# InputModule.net
KiCad netlist of a schematic drawn in Altium Designer
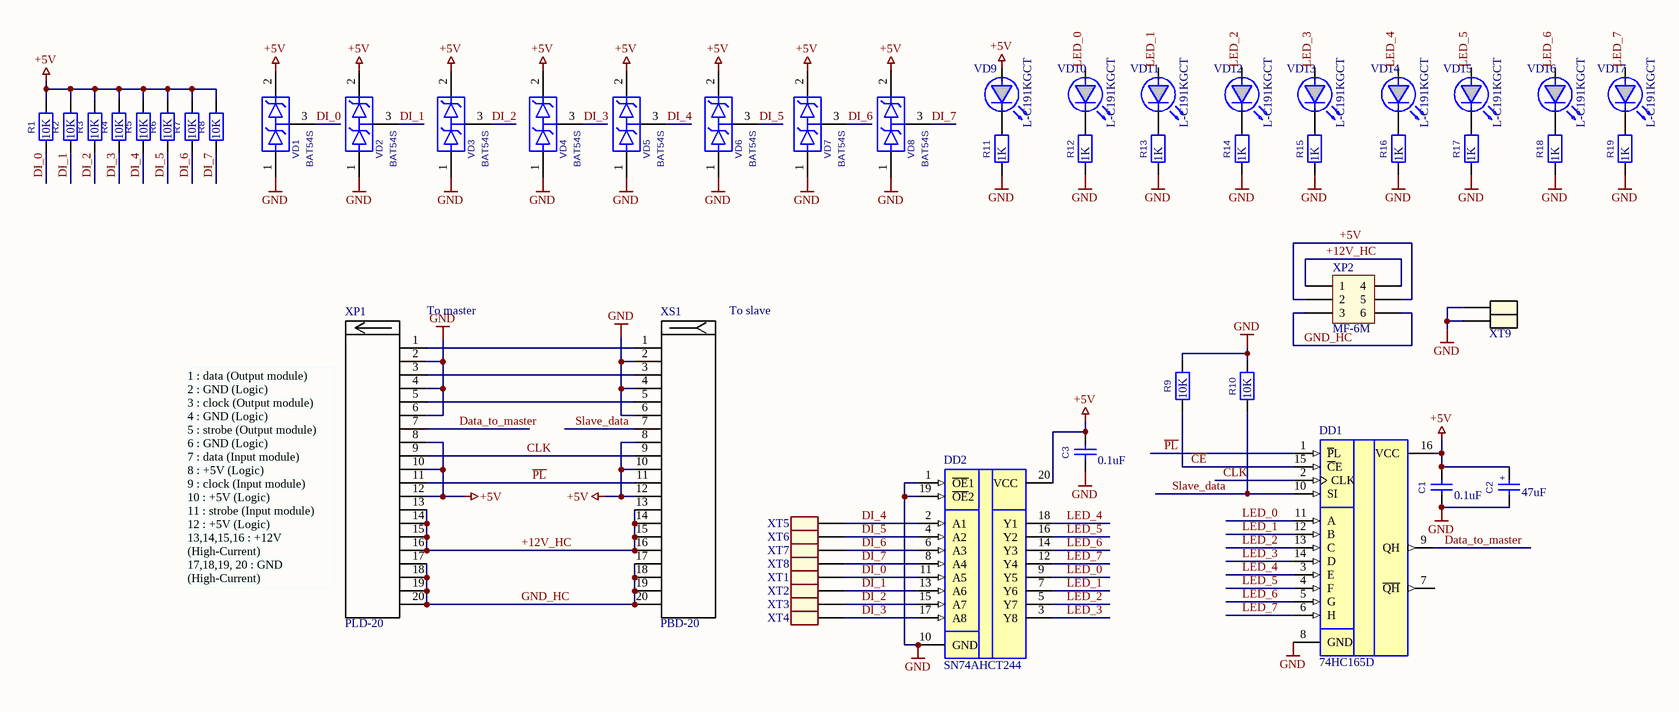
[diagram p0: InputModule.SchDoc]

(export (version "E")
  (design (tool "Eeschema 10.0.6"))
  (components
    (comp (ref "C1")
      (value "0.1uF")
      (footprint "C-1608[0603]")
      (description "C-0603")
      (libsource (lib "Altium-RC") (part "C-0603"))
    )
    (comp (ref "C2")
      (value "47uF")
      (footprint "C-CASE")
      (description "C-CCASE")
      (libsource (lib "Altium-RC") (part "C-CCASE"))
    )
    (comp (ref "C3")
      (value "0.1uF")
      (footprint "C-1608[0603]")
      (description "C-0603")
      (libsource (lib "Altium-RC") (part "C-0603"))
    )
    (comp (ref "DD1")
      (value "74HC165D")
      (footprint "SO-G16")
      (description "8-Bit Parallel-Load Shift Register")
      (libsource (lib "Altium-IC") (part "74HC165D"))
    )
    (comp (ref "DD2")
      (value "SN74AHCT244")
      (footprint "TSSOP20")
      (description "Octal Buffer/Driver with 3-State Outputs")
      (libsource (lib "Altium-IC") (part "SN74LVC244APW"))
    )
    (comp (ref "R1")
      (value "10K")
      (footprint "R-1608[0603]")
      (description "R-0603")
      (libsource (lib "Altium-RC") (part "R-0603"))
    )
    (comp (ref "R2")
      (value "10K")
      (footprint "R-1608[0603]")
      (description "R-0603")
      (libsource (lib "Altium-RC") (part "R-0603"))
    )
    (comp (ref "R3")
      (value "10K")
      (footprint "R-1608[0603]")
      (description "R-0603")
      (libsource (lib "Altium-RC") (part "R-0603"))
    )
    (comp (ref "R4")
      (value "10K")
      (footprint "R-1608[0603]")
      (description "R-0603")
      (libsource (lib "Altium-RC") (part "R-0603"))
    )
    (comp (ref "R5")
      (value "10K")
      (footprint "R-1608[0603]")
      (description "R-0603")
      (libsource (lib "Altium-RC") (part "R-0603"))
    )
    (comp (ref "R6")
      (value "10K")
      (footprint "R-1608[0603]")
      (description "R-0603")
      (libsource (lib "Altium-RC") (part "R-0603"))
    )
    (comp (ref "R7")
      (value "10K")
      (footprint "R-1608[0603]")
      (description "R-0603")
      (libsource (lib "Altium-RC") (part "R-0603"))
    )
    (comp (ref "R8")
      (value "10K")
      (footprint "R-1608[0603]")
      (description "R-0603")
      (libsource (lib "Altium-RC") (part "R-0603"))
    )
    (comp (ref "R9")
      (value "10K")
      (footprint "R-1608[0603]")
      (description "R-0603")
      (libsource (lib "Altium-RC") (part "R-0603"))
    )
    (comp (ref "R10")
      (value "10K")
      (footprint "R-1608[0603]")
      (description "R-0603")
      (libsource (lib "Altium-RC") (part "R-0603"))
    )
    (comp (ref "R11")
      (value "1K")
      (footprint "R-1608[0603]")
      (description "R-0603")
      (libsource (lib "Altium-RC") (part "R-0603"))
    )
    (comp (ref "R12")
      (value "1K")
      (footprint "R-1608[0603]")
      (description "R-0603")
      (libsource (lib "Altium-RC") (part "R-0603"))
    )
    (comp (ref "R13")
      (value "1K")
      (footprint "R-1608[0603]")
      (description "R-0603")
      (libsource (lib "Altium-RC") (part "R-0603"))
    )
    (comp (ref "R14")
      (value "1K")
      (footprint "R-1608[0603]")
      (description "R-0603")
      (libsource (lib "Altium-RC") (part "R-0603"))
    )
    (comp (ref "R15")
      (value "1K")
      (footprint "R-1608[0603]")
      (description "R-0603")
      (libsource (lib "Altium-RC") (part "R-0603"))
    )
    (comp (ref "R16")
      (value "1K")
      (footprint "R-1608[0603]")
      (description "R-0603")
      (libsource (lib "Altium-RC") (part "R-0603"))
    )
    (comp (ref "R17")
      (value "1K")
      (footprint "R-1608[0603]")
      (description "R-0603")
      (libsource (lib "Altium-RC") (part "R-0603"))
    )
    (comp (ref "R18")
      (value "1K")
      (footprint "R-1608[0603]")
      (description "R-0603")
      (libsource (lib "Altium-RC") (part "R-0603"))
    )
    (comp (ref "R19")
      (value "1K")
      (footprint "R-1608[0603]")
      (description "R-0603")
      (libsource (lib "Altium-RC") (part "R-0603"))
    )
    (comp (ref "VD1")
      (value "BAT54S")
      (footprint "SOT-23")
      (description "Schottky barrier (double) diodes")
      (libsource (lib "Altium-RECT") (part "BAT54S"))
    )
    (comp (ref "VD2")
      (value "BAT54S")
      (footprint "SOT-23")
      (description "Schottky barrier (double) diodes")
      (libsource (lib "Altium-RECT") (part "BAT54S"))
    )
    (comp (ref "VD3")
      (value "BAT54S")
      (footprint "SOT-23")
      (description "Schottky barrier (double) diodes")
      (libsource (lib "Altium-RECT") (part "BAT54S"))
    )
    (comp (ref "VD4")
      (value "BAT54S")
      (footprint "SOT-23")
      (description "Schottky barrier (double) diodes")
      (libsource (lib "Altium-RECT") (part "BAT54S"))
    )
    (comp (ref "VD5")
      (value "BAT54S")
      (footprint "SOT-23")
      (description "Schottky barrier (double) diodes")
      (libsource (lib "Altium-RECT") (part "BAT54S"))
    )
    (comp (ref "VD6")
      (value "BAT54S")
      (footprint "SOT-23")
      (description "Schottky barrier (double) diodes")
      (libsource (lib "Altium-RECT") (part "BAT54S"))
    )
    (comp (ref "VD7")
      (value "BAT54S")
      (footprint "SOT-23")
      (description "Schottky barrier (double) diodes")
      (libsource (lib "Altium-RECT") (part "BAT54S"))
    )
    (comp (ref "VD8")
      (value "BAT54S")
      (footprint "SOT-23")
      (description "Schottky barrier (double) diodes")
      (libsource (lib "Altium-RECT") (part "BAT54S"))
    )
    (comp (ref "VD9")
      (value "L-C191KGCT")
      (footprint "LED-0603")
      (description "0603 Green Led")
      (libsource (lib "Altium-OPTO") (part "L-C191KGCT"))
    )
    (comp (ref "VD10")
      (value "L-C191KGCT")
      (footprint "LED-0603")
      (description "0603 Green Led")
      (libsource (lib "Altium-OPTO") (part "L-C191KGCT"))
    )
    (comp (ref "VD11")
      (value "L-C191KGCT")
      (footprint "LED-0603")
      (description "0603 Green Led")
      (libsource (lib "Altium-OPTO") (part "L-C191KGCT"))
    )
    (comp (ref "VD12")
      (value "L-C191KGCT")
      (footprint "LED-0603")
      (description "0603 Green Led")
      (libsource (lib "Altium-OPTO") (part "L-C191KGCT"))
    )
    (comp (ref "VD13")
      (value "L-C191KGCT")
      (footprint "LED-0603")
      (description "0603 Green Led")
      (libsource (lib "Altium-OPTO") (part "L-C191KGCT"))
    )
    (comp (ref "VD14")
      (value "L-C191KGCT")
      (footprint "LED-0603")
      (description "0603 Green Led")
      (libsource (lib "Altium-OPTO") (part "L-C191KGCT"))
    )
    (comp (ref "VD15")
      (value "L-C191KGCT")
      (footprint "LED-0603")
      (description "0603 Green Led")
      (libsource (lib "Altium-OPTO") (part "L-C191KGCT"))
    )
    (comp (ref "VD16")
      (value "L-C191KGCT")
      (footprint "LED-0603")
      (description "0603 Green Led")
      (libsource (lib "Altium-OPTO") (part "L-C191KGCT"))
    )
    (comp (ref "VD17")
      (value "L-C191KGCT")
      (footprint "LED-0603")
      (description "0603 Green Led")
      (libsource (lib "Altium-OPTO") (part "L-C191KGCT"))
    )
    (comp (ref "XP1")
      (value "PLD-20")
      (footprint "PLD-20 ROT")
      (description "20 pin, 2 row, MALE connector")
      (libsource (lib "Altium-CONN") (part "PLD-20"))
    )
    (comp (ref "XP2")
      (value "MF-6M")
      (footprint "MF-6M")
      (description "Molex Male connector")
      (libsource (lib "Altium-CONN") (part "MF-6M"))
    )
    (comp (ref "XS1")
      (value "PBD-20")
      (footprint "PBD-20 Rot")
      (description "2.54mm, 20 pin FEMALE connector")
      (libsource (lib "Altium-CONN") (part "PBD-20"))
    )
    (comp (ref "XT1")
      (value "DG141V-01P")
      (footprint "DG141V-01P (XY123R)")
      (description "Клеммник нажимной 2.54мм")
      (libsource (lib "Altium-CONN") (part "DG141V-01P"))
    )
    (comp (ref "XT2")
      (value "DG141V-01P")
      (footprint "DG141V-01P (XY123R)")
      (description "Клеммник нажимной 2.54мм")
      (libsource (lib "Altium-CONN") (part "DG141V-01P"))
    )
    (comp (ref "XT3")
      (value "DG141V-01P")
      (footprint "DG141V-01P (XY123R)")
      (description "Клеммник нажимной 2.54мм")
      (libsource (lib "Altium-CONN") (part "DG141V-01P"))
    )
    (comp (ref "XT4")
      (value "DG141V-01P")
      (footprint "DG141V-01P (XY123R)")
      (description "Клеммник нажимной 2.54мм")
      (libsource (lib "Altium-CONN") (part "DG141V-01P"))
    )
    (comp (ref "XT5")
      (value "DG141V-01P")
      (footprint "DG141V-01P (XY123R)")
      (description "Клеммник нажимной 2.54мм")
      (libsource (lib "Altium-CONN") (part "DG141V-01P"))
    )
    (comp (ref "XT6")
      (value "DG141V-01P")
      (footprint "DG141V-01P (XY123R)")
      (description "Клеммник нажимной 2.54мм")
      (libsource (lib "Altium-CONN") (part "DG141V-01P"))
    )
    (comp (ref "XT7")
      (value "DG141V-01P")
      (footprint "DG141V-01P (XY123R)")
      (description "Клеммник нажимной 2.54мм")
      (libsource (lib "Altium-CONN") (part "DG141V-01P"))
    )
    (comp (ref "XT8")
      (value "DG141V-01P")
      (footprint "DG141V-01P (XY123R)")
      (description "Клеммник нажимной 2.54мм")
      (libsource (lib "Altium-CONN") (part "DG141V-01P"))
    )
    (comp (ref "XT9")
      (value "1-1776244-0 (TYCO)")
      (footprint "1-1776244-0")
      (description "Винтовой клеммник 5.0мм")
      (libsource (lib "Altium-CONN") (part "1-1776244-0 (TYCO)"))
    )
  )
  (nets
    (net (code "1") (name "+5V") (class "Default")
      (node (ref "C1") (pin "1") (pintype "passive"))
      (node (ref "C2") (pin "1") (pinfunction "+_1") (pintype "passive"))
      (node (ref "C3") (pin "1") (pintype "passive"))
      (node (ref "DD1") (pin "16") (pinfunction "VCC_16") (pintype "power_in"))
      (node (ref "DD2") (pin "20") (pinfunction "VCC_20") (pintype "power_in"))
      (node (ref "R1") (pin "2") (pinfunction "2_2") (pintype "passive"))
      (node (ref "R2") (pin "2") (pinfunction "2_2") (pintype "passive"))
      (node (ref "R3") (pin "2") (pinfunction "2_2") (pintype "passive"))
      (node (ref "R4") (pin "2") (pinfunction "2_2") (pintype "passive"))
      (node (ref "R5") (pin "2") (pinfunction "2_2") (pintype "passive"))
      (node (ref "R6") (pin "2") (pinfunction "2_2") (pintype "passive"))
      (node (ref "R7") (pin "2") (pinfunction "2_2") (pintype "passive"))
      (node (ref "R8") (pin "2") (pinfunction "2_2") (pintype "passive"))
      (node (ref "VD1") (pin "2") (pinfunction "c_2") (pintype "passive"))
      (node (ref "VD2") (pin "2") (pinfunction "c_2") (pintype "passive"))
      (node (ref "VD3") (pin "2") (pinfunction "c_2") (pintype "passive"))
      (node (ref "VD4") (pin "2") (pinfunction "c_2") (pintype "passive"))
      (node (ref "VD5") (pin "2") (pinfunction "c_2") (pintype "passive"))
      (node (ref "VD6") (pin "2") (pinfunction "c_2") (pintype "passive"))
      (node (ref "VD7") (pin "2") (pinfunction "c_2") (pintype "passive"))
      (node (ref "VD8") (pin "2") (pinfunction "c_2") (pintype "passive"))
      (node (ref "VD9") (pin "2") (pinfunction "A_2") (pintype "passive"))
      (node (ref "XP1") (pin "10") (pintype "passive"))
      (node (ref "XP1") (pin "12") (pintype "passive"))
      (node (ref "XP1") (pin "8") (pintype "passive"))
      (node (ref "XP2") (pin "2") (pinfunction "2_2") (pintype "passive"))
      (node (ref "XP2") (pin "5") (pinfunction "5_5") (pintype "passive"))
      (node (ref "XS1") (pin "10") (pintype "passive"))
      (node (ref "XS1") (pin "12") (pintype "passive"))
      (node (ref "XS1") (pin "8") (pintype "passive"))
    )
    (net (code "2") (name "/+12V_HC") (class "Default")
      (node (ref "XP1") (pin "13") (pintype "passive"))
      (node (ref "XP1") (pin "14") (pintype "passive"))
      (node (ref "XP1") (pin "15") (pintype "passive"))
      (node (ref "XP1") (pin "16") (pintype "passive"))
      (node (ref "XP2") (pin "1") (pinfunction "1_1") (pintype "passive"))
      (node (ref "XP2") (pin "4") (pinfunction "4_4") (pintype "passive"))
      (node (ref "XS1") (pin "13") (pintype "passive"))
      (node (ref "XS1") (pin "14") (pintype "passive"))
      (node (ref "XS1") (pin "15") (pintype "passive"))
      (node (ref "XS1") (pin "16") (pintype "passive"))
    )
    (net (code "3") (name "/CLK") (class "Default")
      (node (ref "DD1") (pin "2") (pinfunction "CLK_2") (pintype "input"))
      (node (ref "XP1") (pin "9") (pintype "passive"))
      (node (ref "XS1") (pin "9") (pintype "passive"))
    )
    (net (code "4") (name "/DI_0") (class "Default")
      (node (ref "DD2") (pin "11") (pinfunction "A5_11") (pintype "input"))
      (node (ref "R1") (pin "1") (pinfunction "1_1") (pintype "passive"))
      (node (ref "VD1") (pin "3") (pinfunction "ka_3") (pintype "passive"))
      (node (ref "XT1") (pin "1") (pintype "passive"))
    )
    (net (code "5") (name "/DI_1") (class "Default")
      (node (ref "DD2") (pin "13") (pinfunction "A6_13") (pintype "input"))
      (node (ref "R2") (pin "1") (pinfunction "1_1") (pintype "passive"))
      (node (ref "VD2") (pin "3") (pinfunction "ka_3") (pintype "passive"))
      (node (ref "XT2") (pin "1") (pintype "passive"))
    )
    (net (code "6") (name "/DI_2") (class "Default")
      (node (ref "DD2") (pin "15") (pinfunction "A7_15") (pintype "input"))
      (node (ref "R3") (pin "1") (pinfunction "1_1") (pintype "passive"))
      (node (ref "VD3") (pin "3") (pinfunction "ka_3") (pintype "passive"))
      (node (ref "XT3") (pin "1") (pintype "passive"))
    )
    (net (code "7") (name "/DI_3") (class "Default")
      (node (ref "DD2") (pin "17") (pinfunction "A8_17") (pintype "input"))
      (node (ref "R4") (pin "1") (pinfunction "1_1") (pintype "passive"))
      (node (ref "VD4") (pin "3") (pinfunction "ka_3") (pintype "passive"))
      (node (ref "XT4") (pin "1") (pintype "passive"))
    )
    (net (code "8") (name "/DI_4") (class "Default")
      (node (ref "DD2") (pin "2") (pinfunction "A1_2") (pintype "input"))
      (node (ref "R5") (pin "1") (pinfunction "1_1") (pintype "passive"))
      (node (ref "VD5") (pin "3") (pinfunction "ka_3") (pintype "passive"))
      (node (ref "XT5") (pin "1") (pintype "passive"))
    )
    (net (code "9") (name "/DI_5") (class "Default")
      (node (ref "DD2") (pin "4") (pinfunction "A2_4") (pintype "input"))
      (node (ref "R6") (pin "1") (pinfunction "1_1") (pintype "passive"))
      (node (ref "VD6") (pin "3") (pinfunction "ka_3") (pintype "passive"))
      (node (ref "XT6") (pin "1") (pintype "passive"))
    )
    (net (code "10") (name "/DI_6") (class "Default")
      (node (ref "DD2") (pin "6") (pinfunction "A3_6") (pintype "input"))
      (node (ref "R7") (pin "1") (pinfunction "1_1") (pintype "passive"))
      (node (ref "VD7") (pin "3") (pinfunction "ka_3") (pintype "passive"))
      (node (ref "XT7") (pin "1") (pintype "passive"))
    )
    (net (code "11") (name "/DI_7") (class "Default")
      (node (ref "DD2") (pin "8") (pinfunction "A4_8") (pintype "input"))
      (node (ref "R8") (pin "1") (pinfunction "1_1") (pintype "passive"))
      (node (ref "VD8") (pin "3") (pinfunction "ka_3") (pintype "passive"))
      (node (ref "XT8") (pin "1") (pintype "passive"))
    )
    (net (code "12") (name "/Data_to_master") (class "Default")
      (node (ref "DD1") (pin "9") (pinfunction "QH_9") (pintype "output"))
      (node (ref "XP1") (pin "7") (pintype "passive"))
    )
    (net (code "13") (name "/GND_HC") (class "Default")
      (node (ref "XP1") (pin "17") (pintype "passive"))
      (node (ref "XP1") (pin "18") (pintype "passive"))
      (node (ref "XP1") (pin "19") (pintype "passive"))
      (node (ref "XP1") (pin "20") (pintype "passive"))
      (node (ref "XP2") (pin "3") (pinfunction "3_3") (pintype "passive"))
      (node (ref "XP2") (pin "6") (pinfunction "6_6") (pintype "passive"))
      (node (ref "XS1") (pin "17") (pintype "passive"))
      (node (ref "XS1") (pin "18") (pintype "passive"))
      (node (ref "XS1") (pin "19") (pintype "passive"))
      (node (ref "XS1") (pin "20") (pintype "passive"))
    )
    (net (code "14") (name "/LED_0") (class "Default")
      (node (ref "DD1") (pin "11") (pinfunction "A_11") (pintype "input"))
      (node (ref "DD2") (pin "9") (pinfunction "Y5_9") (pintype "tri_state"))
      (node (ref "VD10") (pin "2") (pinfunction "A_2") (pintype "passive"))
    )
    (net (code "15") (name "/LED_1") (class "Default")
      (node (ref "DD1") (pin "12") (pinfunction "B_12") (pintype "input"))
      (node (ref "DD2") (pin "7") (pinfunction "Y6_7") (pintype "tri_state"))
      (node (ref "VD11") (pin "2") (pinfunction "A_2") (pintype "passive"))
    )
    (net (code "16") (name "/LED_2") (class "Default")
      (node (ref "DD1") (pin "13") (pinfunction "C_13") (pintype "input"))
      (node (ref "DD2") (pin "5") (pinfunction "Y7_5") (pintype "tri_state"))
      (node (ref "VD12") (pin "2") (pinfunction "A_2") (pintype "passive"))
    )
    (net (code "17") (name "/LED_3") (class "Default")
      (node (ref "DD1") (pin "14") (pinfunction "D_14") (pintype "input"))
      (node (ref "DD2") (pin "3") (pinfunction "Y8_3") (pintype "tri_state"))
      (node (ref "VD13") (pin "2") (pinfunction "A_2") (pintype "passive"))
    )
    (net (code "18") (name "/LED_4") (class "Default")
      (node (ref "DD1") (pin "3") (pinfunction "E_3") (pintype "input"))
      (node (ref "DD2") (pin "18") (pinfunction "Y1_18") (pintype "tri_state"))
      (node (ref "VD14") (pin "2") (pinfunction "A_2") (pintype "passive"))
    )
    (net (code "19") (name "/LED_5") (class "Default")
      (node (ref "DD1") (pin "4") (pinfunction "F_4") (pintype "input"))
      (node (ref "DD2") (pin "16") (pinfunction "Y2_16") (pintype "tri_state"))
      (node (ref "VD15") (pin "2") (pinfunction "A_2") (pintype "passive"))
    )
    (net (code "20") (name "/LED_6") (class "Default")
      (node (ref "DD1") (pin "5") (pinfunction "G_5") (pintype "input"))
      (node (ref "DD2") (pin "14") (pinfunction "Y3_14") (pintype "tri_state"))
      (node (ref "VD16") (pin "2") (pinfunction "A_2") (pintype "passive"))
    )
    (net (code "21") (name "/LED_7") (class "Default")
      (node (ref "DD1") (pin "6") (pinfunction "H_6") (pintype "input"))
      (node (ref "DD2") (pin "12") (pinfunction "Y4_12") (pintype "tri_state"))
      (node (ref "VD17") (pin "2") (pinfunction "A_2") (pintype "passive"))
    )
    (net (code "22") (name "/Slave_data") (class "Default")
      (node (ref "DD1") (pin "10") (pinfunction "SI_10") (pintype "input"))
      (node (ref "R10") (pin "1") (pinfunction "1_1") (pintype "passive"))
      (node (ref "XS1") (pin "7") (pintype "passive"))
    )
    (net (code "23") (name "/~{CE}") (class "Default")
      (node (ref "DD1") (pin "15") (pinfunction "~{C}E_15") (pintype "input"))
      (node (ref "R9") (pin "1") (pinfunction "1_1") (pintype "passive"))
    )
    (net (code "24") (name "/~{PL}") (class "Default")
      (node (ref "DD1") (pin "1") (pinfunction "~{P}L_1") (pintype "input"))
      (node (ref "XP1") (pin "11") (pintype "passive"))
      (node (ref "XS1") (pin "11") (pintype "passive"))
    )
    (net (code "25") (name "GND") (class "Default")
      (node (ref "C1") (pin "2") (pintype "passive"))
      (node (ref "C2") (pin "2") (pinfunction "-_2") (pintype "passive"))
      (node (ref "C3") (pin "2") (pintype "passive"))
      (node (ref "DD1") (pin "8") (pinfunction "GND_8") (pintype "power_in"))
      (node (ref "DD2") (pin "1") (pinfunction "~{OE}1_1") (pintype "input"))
      (node (ref "DD2") (pin "10") (pinfunction "GND_10") (pintype "power_in"))
      (node (ref "DD2") (pin "19") (pinfunction "~{OE}2_19") (pintype "input"))
      (node (ref "R10") (pin "2") (pinfunction "2_2") (pintype "passive"))
      (node (ref "R11") (pin "1") (pinfunction "1_1") (pintype "passive"))
      (node (ref "R12") (pin "1") (pinfunction "1_1") (pintype "passive"))
      (node (ref "R13") (pin "1") (pinfunction "1_1") (pintype "passive"))
      (node (ref "R14") (pin "1") (pinfunction "1_1") (pintype "passive"))
      (node (ref "R15") (pin "1") (pinfunction "1_1") (pintype "passive"))
      (node (ref "R16") (pin "1") (pinfunction "1_1") (pintype "passive"))
      (node (ref "R17") (pin "1") (pinfunction "1_1") (pintype "passive"))
      (node (ref "R18") (pin "1") (pinfunction "1_1") (pintype "passive"))
      (node (ref "R19") (pin "1") (pinfunction "1_1") (pintype "passive"))
      (node (ref "R9") (pin "2") (pinfunction "2_2") (pintype "passive"))
      (node (ref "VD1") (pin "1") (pinfunction "a_1") (pintype "passive"))
      (node (ref "VD2") (pin "1") (pinfunction "a_1") (pintype "passive"))
      (node (ref "VD3") (pin "1") (pinfunction "a_1") (pintype "passive"))
      (node (ref "VD4") (pin "1") (pinfunction "a_1") (pintype "passive"))
      (node (ref "VD5") (pin "1") (pinfunction "a_1") (pintype "passive"))
      (node (ref "VD6") (pin "1") (pinfunction "a_1") (pintype "passive"))
      (node (ref "VD7") (pin "1") (pinfunction "a_1") (pintype "passive"))
      (node (ref "VD8") (pin "1") (pinfunction "a_1") (pintype "passive"))
      (node (ref "XP1") (pin "2") (pintype "passive"))
      (node (ref "XP1") (pin "4") (pintype "passive"))
      (node (ref "XP1") (pin "6") (pintype "passive"))
      (node (ref "XS1") (pin "2") (pintype "passive"))
      (node (ref "XS1") (pin "4") (pintype "passive"))
      (node (ref "XS1") (pin "6") (pintype "passive"))
      (node (ref "XT9") (pin "1") (pintype "passive"))
      (node (ref "XT9") (pin "2") (pintype "passive"))
    )
    (net (code "26") (name "Net-(VD9-K)") (class "Default")
      (node (ref "R11") (pin "2") (pinfunction "2_2") (pintype "passive"))
      (node (ref "VD9") (pin "1") (pinfunction "K_1") (pintype "passive"))
    )
    (net (code "27") (name "Net-(VD10-K)") (class "Default")
      (node (ref "R12") (pin "2") (pinfunction "2_2") (pintype "passive"))
      (node (ref "VD10") (pin "1") (pinfunction "K_1") (pintype "passive"))
    )
    (net (code "28") (name "Net-(VD11-K)") (class "Default")
      (node (ref "R13") (pin "2") (pinfunction "2_2") (pintype "passive"))
      (node (ref "VD11") (pin "1") (pinfunction "K_1") (pintype "passive"))
    )
    (net (code "29") (name "Net-(VD12-K)") (class "Default")
      (node (ref "R14") (pin "2") (pinfunction "2_2") (pintype "passive"))
      (node (ref "VD12") (pin "1") (pinfunction "K_1") (pintype "passive"))
    )
    (net (code "30") (name "Net-(VD13-K)") (class "Default")
      (node (ref "R15") (pin "2") (pinfunction "2_2") (pintype "passive"))
      (node (ref "VD13") (pin "1") (pinfunction "K_1") (pintype "passive"))
    )
    (net (code "31") (name "Net-(VD14-K)") (class "Default")
      (node (ref "R16") (pin "2") (pinfunction "2_2") (pintype "passive"))
      (node (ref "VD14") (pin "1") (pinfunction "K_1") (pintype "passive"))
    )
    (net (code "32") (name "Net-(VD15-K)") (class "Default")
      (node (ref "R17") (pin "2") (pinfunction "2_2") (pintype "passive"))
      (node (ref "VD15") (pin "1") (pinfunction "K_1") (pintype "passive"))
    )
    (net (code "33") (name "Net-(VD16-K)") (class "Default")
      (node (ref "R18") (pin "2") (pinfunction "2_2") (pintype "passive"))
      (node (ref "VD16") (pin "1") (pinfunction "K_1") (pintype "passive"))
    )
    (net (code "34") (name "Net-(VD17-K)") (class "Default")
      (node (ref "R19") (pin "2") (pinfunction "2_2") (pintype "passive"))
      (node (ref "VD17") (pin "1") (pinfunction "K_1") (pintype "passive"))
    )
    (net (code "35") (name "Net-(XP1-Pad1)") (class "Default")
      (node (ref "XP1") (pin "1") (pintype "passive"))
      (node (ref "XS1") (pin "1") (pintype "passive"))
    )
    (net (code "36") (name "Net-(XP1-Pad3)") (class "Default")
      (node (ref "XP1") (pin "3") (pintype "passive"))
      (node (ref "XS1") (pin "3") (pintype "passive"))
    )
    (net (code "37") (name "Net-(XP1-Pad5)") (class "Default")
      (node (ref "XP1") (pin "5") (pintype "passive"))
      (node (ref "XS1") (pin "5") (pintype "passive"))
    )
    (net (code "38") (name "unconnected-(DD1-~{QH}-Pad7)") (class "Default")
      (node (ref "DD1") (pin "7") (pinfunction "~{QH}_7") (pintype "output"))
    )
  )
)
